# Sheet1.net
KiCad netlist of a schematic drawn in Altium Designer
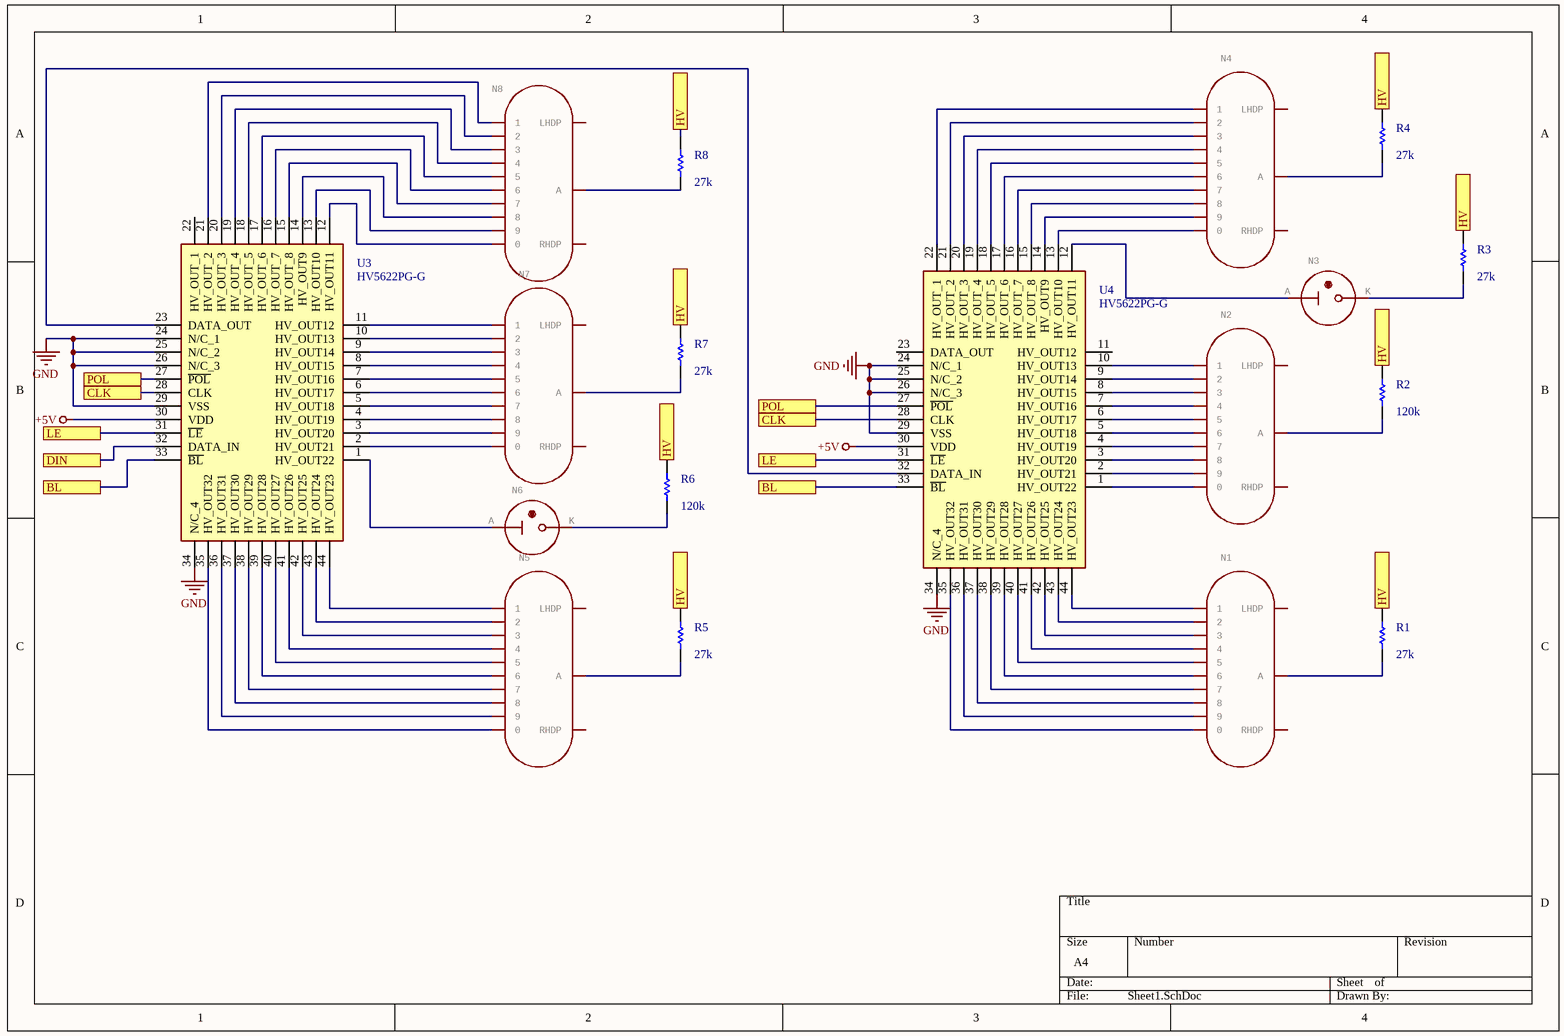
[diagram p0: Sheet1.SchDoc]

(export (version "E")
  (design (tool "Eeschema 10.0.6"))
  (components
    (comp (ref "N1")
      (value "IN-14: medium numeric frontview nixie tube")
      (footprint "IN-14")
      (fields (field (name "LIBRARYNAME") "nixies-us"))
      (libsource (lib "nixies-us.Library") (part "IN-14"))
    )
    (comp (ref "N2")
      (value "IN-14: medium numeric frontview nixie tube")
      (footprint "IN-14")
      (fields (field (name "LIBRARYNAME") "nixies-us"))
      (libsource (lib "nixies-us.Library") (part "IN-14"))
    )
    (comp (ref "N3")
      (value "IN-3: nixie bulb")
      (footprint "IN-3")
      (fields (field (name "LIBRARYNAME") "nixies-us"))
      (libsource (lib "nixies-us.Library") (part "IN-3"))
    )
    (comp (ref "N4")
      (value "IN-14: medium numeric frontview nixie tube")
      (footprint "IN-14")
      (fields (field (name "LIBRARYNAME") "nixies-us"))
      (libsource (lib "nixies-us.Library") (part "IN-14"))
    )
    (comp (ref "N5")
      (value "IN-14: medium numeric frontview nixie tube")
      (footprint "IN-14")
      (fields (field (name "LIBRARYNAME") "nixies-us"))
      (libsource (lib "nixies-us.Library") (part "IN-14"))
    )
    (comp (ref "N6")
      (value "IN-3: nixie bulb")
      (footprint "IN-3")
      (fields (field (name "LIBRARYNAME") "nixies-us"))
      (libsource (lib "nixies-us.Library") (part "IN-3"))
    )
    (comp (ref "N7")
      (value "IN-14: medium numeric frontview nixie tube")
      (footprint "IN-14")
      (fields (field (name "LIBRARYNAME") "nixies-us"))
      (libsource (lib "nixies-us.Library") (part "IN-14"))
    )
    (comp (ref "N8")
      (value "IN-14: medium numeric frontview nixie tube")
      (footprint "IN-14")
      (fields (field (name "LIBRARYNAME") "nixies-us"))
      (libsource (lib "nixies-us.Library") (part "IN-14"))
    )
    (comp (ref "R1")
      (value "27k")
      (footprint "AXIAL-0.3")
      (description "Resistor")
      (fields (field (name "PUBLISHER") "Altium Limited"))
      (libsource (lib "Miscellaneous Devices") (part "Res1"))
    )
    (comp (ref "R2")
      (value "120k")
      (footprint "AXIAL-0.3")
      (description "Resistor")
      (fields (field (name "PUBLISHER") "Altium Limited"))
      (libsource (lib "Miscellaneous Devices") (part "Res1"))
    )
    (comp (ref "R3")
      (value "27k")
      (footprint "AXIAL-0.3")
      (description "Resistor")
      (fields (field (name "PUBLISHER") "Altium Limited"))
      (libsource (lib "Miscellaneous Devices") (part "Res1"))
    )
    (comp (ref "R4")
      (value "27k")
      (footprint "AXIAL-0.3")
      (description "Resistor")
      (fields (field (name "PUBLISHER") "Altium Limited"))
      (libsource (lib "Miscellaneous Devices") (part "Res1"))
    )
    (comp (ref "R5")
      (value "27k")
      (footprint "AXIAL-0.3")
      (description "Resistor")
      (fields (field (name "PUBLISHER") "Altium Limited"))
      (libsource (lib "Miscellaneous Devices") (part "Res1"))
    )
    (comp (ref "R6")
      (value "120k")
      (footprint "AXIAL-0.3")
      (description "Resistor")
      (fields (field (name "PUBLISHER") "Altium Limited"))
      (libsource (lib "Miscellaneous Devices") (part "Res1"))
    )
    (comp (ref "R7")
      (value "27k")
      (footprint "AXIAL-0.3")
      (description "Resistor")
      (fields (field (name "PUBLISHER") "Altium Limited"))
      (libsource (lib "Miscellaneous Devices") (part "Res1"))
    )
    (comp (ref "R8")
      (value "27k")
      (footprint "AXIAL-0.3")
      (description "Resistor")
      (fields (field (name "PUBLISHER") "Altium Limited"))
      (libsource (lib "Miscellaneous Devices") (part "Res1"))
    )
    (comp (ref "U3")
      (value "HV5622PG-G")
      (footprint "SamacSys:QFP80P1390X1390X235-44N")
      (description "Integrated Circuit")
      (fields (field (name "MOUSER PART NUMBER") "689-HV5622PG-G"))
      (libsource (lib "*") (part "HV5622PG-G"))
    )
    (comp (ref "U4")
      (value "HV5622PG-G")
      (footprint "SamacSys:QFP80P1390X1390X235-44N")
      (description "Integrated Circuit")
      (fields (field (name "MOUSER PART NUMBER") "689-HV5622PG-G"))
      (libsource (lib "*") (part "HV5622PG-G"))
    )
  )
  (nets
    (net (code "1") (name "+5V") (class "Default")
      (node (ref "U3") (pin "30") (pinfunction "VDD_30") (pintype "passive"))
      (node (ref "U4") (pin "30") (pinfunction "VDD_30") (pintype "passive"))
    )
    (net (code "2") (name "/BL") (class "Default")
      (node (ref "U3") (pin "33") (pinfunction "~{BL}_33") (pintype "passive"))
      (node (ref "U4") (pin "33") (pinfunction "~{BL}_33") (pintype "passive"))
    )
    (net (code "3") (name "/CLK") (class "Default")
      (node (ref "U3") (pin "28") (pinfunction "CLK_28") (pintype "passive"))
      (node (ref "U4") (pin "28") (pinfunction "CLK_28") (pintype "passive"))
    )
    (net (code "4") (name "/DIN") (class "Default")
      (node (ref "U3") (pin "32") (pinfunction "DATA_IN_32") (pintype "passive"))
    )
    (net (code "5") (name "/HV") (class "Default")
      (node (ref "R1") (pin "1") (pinfunction "1_1") (pintype "passive"))
      (node (ref "R2") (pin "1") (pinfunction "1_1") (pintype "passive"))
      (node (ref "R3") (pin "1") (pinfunction "1_1") (pintype "passive"))
      (node (ref "R4") (pin "1") (pinfunction "1_1") (pintype "passive"))
      (node (ref "R5") (pin "1") (pinfunction "1_1") (pintype "passive"))
      (node (ref "R6") (pin "1") (pinfunction "1_1") (pintype "passive"))
      (node (ref "R7") (pin "1") (pinfunction "1_1") (pintype "passive"))
      (node (ref "R8") (pin "1") (pinfunction "1_1") (pintype "passive"))
    )
    (net (code "6") (name "/LE") (class "Default")
      (node (ref "U3") (pin "31") (pinfunction "~{LE}_31") (pintype "passive"))
      (node (ref "U4") (pin "31") (pinfunction "~{LE}_31") (pintype "passive"))
    )
    (net (code "7") (name "/POL") (class "Default")
      (node (ref "U3") (pin "27") (pinfunction "~{POL}_27") (pintype "passive"))
      (node (ref "U4") (pin "27") (pinfunction "~{POL}_27") (pintype "passive"))
    )
    (net (code "8") (name "GND") (class "Default")
      (node (ref "U3") (pin "24") (pinfunction "N/C_1_24") (pintype "passive"))
      (node (ref "U3") (pin "25") (pinfunction "N/C_2_25") (pintype "passive"))
      (node (ref "U3") (pin "26") (pinfunction "N/C_3_26") (pintype "passive"))
      (node (ref "U3") (pin "29") (pinfunction "VSS_29") (pintype "passive"))
      (node (ref "U3") (pin "34") (pinfunction "N/C_4_34") (pintype "passive"))
      (node (ref "U4") (pin "24") (pinfunction "N/C_1_24") (pintype "passive"))
      (node (ref "U4") (pin "25") (pinfunction "N/C_2_25") (pintype "passive"))
      (node (ref "U4") (pin "26") (pinfunction "N/C_3_26") (pintype "passive"))
      (node (ref "U4") (pin "29") (pinfunction "VSS_29") (pintype "passive"))
      (node (ref "U4") (pin "34") (pinfunction "N/C_4_34") (pintype "passive"))
    )
    (net (code "9") (name "Net-(N1-PadA)") (class "Default")
      (node (ref "N1") (pin "A") (pinfunction "A_A") (pintype "bidirectional"))
      (node (ref "R1") (pin "2") (pinfunction "2_2") (pintype "passive"))
    )
    (net (code "10") (name "Net-(N2-PadA)") (class "Default")
      (node (ref "N2") (pin "A") (pinfunction "A_A") (pintype "bidirectional"))
      (node (ref "R2") (pin "2") (pinfunction "2_2") (pintype "passive"))
    )
    (net (code "11") (name "Net-(N3-PadK)") (class "Default")
      (node (ref "N3") (pin "K") (pinfunction "K_K") (pintype "bidirectional"))
      (node (ref "R3") (pin "2") (pinfunction "2_2") (pintype "passive"))
    )
    (net (code "12") (name "Net-(N4-PadA)") (class "Default")
      (node (ref "N4") (pin "A") (pinfunction "A_A") (pintype "bidirectional"))
      (node (ref "R4") (pin "2") (pinfunction "2_2") (pintype "passive"))
    )
    (net (code "13") (name "Net-(N5-PadA)") (class "Default")
      (node (ref "N5") (pin "A") (pinfunction "A_A") (pintype "bidirectional"))
      (node (ref "R5") (pin "2") (pinfunction "2_2") (pintype "passive"))
    )
    (net (code "14") (name "Net-(N6-PadK)") (class "Default")
      (node (ref "N6") (pin "K") (pinfunction "K_K") (pintype "bidirectional"))
      (node (ref "R6") (pin "2") (pinfunction "2_2") (pintype "passive"))
    )
    (net (code "15") (name "Net-(N7-PadA)") (class "Default")
      (node (ref "N7") (pin "A") (pinfunction "A_A") (pintype "bidirectional"))
      (node (ref "R7") (pin "2") (pinfunction "2_2") (pintype "passive"))
    )
    (net (code "16") (name "Net-(N8-PadA)") (class "Default")
      (node (ref "N8") (pin "A") (pinfunction "A_A") (pintype "bidirectional"))
      (node (ref "R8") (pin "2") (pinfunction "2_2") (pintype "passive"))
    )
    (net (code "17") (name "Net-(U3-DATA_OUT)") (class "Default")
      (node (ref "U3") (pin "23") (pinfunction "DATA_OUT_23") (pintype "passive"))
      (node (ref "U4") (pin "32") (pinfunction "DATA_IN_32") (pintype "passive"))
    )
    (net (code "18") (name "Net-(U3-HV_OUT9)") (class "Default")
      (node (ref "N8") (pin "8") (pinfunction "8_8") (pintype "bidirectional"))
      (node (ref "U3") (pin "14") (pinfunction "HV_OUT9_14") (pintype "passive"))
    )
    (net (code "19") (name "Net-(U3-HV_OUT10)") (class "Default")
      (node (ref "N8") (pin "9") (pinfunction "9_9") (pintype "bidirectional"))
      (node (ref "U3") (pin "13") (pinfunction "HV_OUT10_13") (pintype "passive"))
    )
    (net (code "20") (name "Net-(U3-HV_OUT11)") (class "Default")
      (node (ref "N8") (pin "0") (pinfunction "0_0") (pintype "bidirectional"))
      (node (ref "U3") (pin "12") (pinfunction "HV_OUT11_12") (pintype "passive"))
    )
    (net (code "21") (name "Net-(U3-HV_OUT12)") (class "Default")
      (node (ref "N7") (pin "1") (pinfunction "1_1") (pintype "bidirectional"))
      (node (ref "U3") (pin "11") (pinfunction "HV_OUT12_11") (pintype "passive"))
    )
    (net (code "22") (name "Net-(U3-HV_OUT13)") (class "Default")
      (node (ref "N7") (pin "2") (pinfunction "2_2") (pintype "bidirectional"))
      (node (ref "U3") (pin "10") (pinfunction "HV_OUT13_10") (pintype "passive"))
    )
    (net (code "23") (name "Net-(U3-HV_OUT14)") (class "Default")
      (node (ref "N7") (pin "3") (pinfunction "3_3") (pintype "bidirectional"))
      (node (ref "U3") (pin "9") (pinfunction "HV_OUT14_9") (pintype "passive"))
    )
    (net (code "24") (name "Net-(U3-HV_OUT15)") (class "Default")
      (node (ref "N7") (pin "4") (pinfunction "4_4") (pintype "bidirectional"))
      (node (ref "U3") (pin "8") (pinfunction "HV_OUT15_8") (pintype "passive"))
    )
    (net (code "25") (name "Net-(U3-HV_OUT16)") (class "Default")
      (node (ref "N7") (pin "5") (pinfunction "5_5") (pintype "bidirectional"))
      (node (ref "U3") (pin "7") (pinfunction "HV_OUT16_7") (pintype "passive"))
    )
    (net (code "26") (name "Net-(U3-HV_OUT17)") (class "Default")
      (node (ref "N7") (pin "6") (pinfunction "6_6") (pintype "bidirectional"))
      (node (ref "U3") (pin "6") (pinfunction "HV_OUT17_6") (pintype "passive"))
    )
    (net (code "27") (name "Net-(U3-HV_OUT18)") (class "Default")
      (node (ref "N7") (pin "7") (pinfunction "7_7") (pintype "bidirectional"))
      (node (ref "U3") (pin "5") (pinfunction "HV_OUT18_5") (pintype "passive"))
    )
    (net (code "28") (name "Net-(U3-HV_OUT19)") (class "Default")
      (node (ref "N7") (pin "8") (pinfunction "8_8") (pintype "bidirectional"))
      (node (ref "U3") (pin "4") (pinfunction "HV_OUT19_4") (pintype "passive"))
    )
    (net (code "29") (name "Net-(U3-HV_OUT20)") (class "Default")
      (node (ref "N7") (pin "9") (pinfunction "9_9") (pintype "bidirectional"))
      (node (ref "U3") (pin "3") (pinfunction "HV_OUT20_3") (pintype "passive"))
    )
    (net (code "30") (name "Net-(U3-HV_OUT21)") (class "Default")
      (node (ref "N7") (pin "0") (pinfunction "0_0") (pintype "bidirectional"))
      (node (ref "U3") (pin "2") (pinfunction "HV_OUT21_2") (pintype "passive"))
    )
    (net (code "31") (name "Net-(U3-HV_OUT22)") (class "Default")
      (node (ref "N6") (pin "A") (pinfunction "A_A") (pintype "bidirectional"))
      (node (ref "U3") (pin "1") (pinfunction "HV_OUT22_1") (pintype "passive"))
    )
    (net (code "32") (name "Net-(U3-HV_OUT23)") (class "Default")
      (node (ref "N5") (pin "1") (pinfunction "1_1") (pintype "bidirectional"))
      (node (ref "U3") (pin "44") (pinfunction "HV_OUT23_44") (pintype "passive"))
    )
    (net (code "33") (name "Net-(U3-HV_OUT24)") (class "Default")
      (node (ref "N5") (pin "2") (pinfunction "2_2") (pintype "bidirectional"))
      (node (ref "U3") (pin "43") (pinfunction "HV_OUT24_43") (pintype "passive"))
    )
    (net (code "34") (name "Net-(U3-HV_OUT25)") (class "Default")
      (node (ref "N5") (pin "3") (pinfunction "3_3") (pintype "bidirectional"))
      (node (ref "U3") (pin "42") (pinfunction "HV_OUT25_42") (pintype "passive"))
    )
    (net (code "35") (name "Net-(U3-HV_OUT26)") (class "Default")
      (node (ref "N5") (pin "4") (pinfunction "4_4") (pintype "bidirectional"))
      (node (ref "U3") (pin "41") (pinfunction "HV_OUT26_41") (pintype "passive"))
    )
    (net (code "36") (name "Net-(U3-HV_OUT27)") (class "Default")
      (node (ref "N5") (pin "5") (pinfunction "5_5") (pintype "bidirectional"))
      (node (ref "U3") (pin "40") (pinfunction "HV_OUT27_40") (pintype "passive"))
    )
    (net (code "37") (name "Net-(U3-HV_OUT28)") (class "Default")
      (node (ref "N5") (pin "6") (pinfunction "6_6") (pintype "bidirectional"))
      (node (ref "U3") (pin "39") (pinfunction "HV_OUT28_39") (pintype "passive"))
    )
    (net (code "38") (name "Net-(U3-HV_OUT29)") (class "Default")
      (node (ref "N5") (pin "7") (pinfunction "7_7") (pintype "bidirectional"))
      (node (ref "U3") (pin "38") (pinfunction "HV_OUT29_38") (pintype "passive"))
    )
    (net (code "39") (name "Net-(U3-HV_OUT30)") (class "Default")
      (node (ref "N5") (pin "8") (pinfunction "8_8") (pintype "bidirectional"))
      (node (ref "U3") (pin "37") (pinfunction "HV_OUT30_37") (pintype "passive"))
    )
    (net (code "40") (name "Net-(U3-HV_OUT31)") (class "Default")
      (node (ref "N5") (pin "9") (pinfunction "9_9") (pintype "bidirectional"))
      (node (ref "U3") (pin "36") (pinfunction "HV_OUT31_36") (pintype "passive"))
    )
    (net (code "41") (name "Net-(U3-HV_OUT32)") (class "Default")
      (node (ref "N5") (pin "0") (pinfunction "0_0") (pintype "bidirectional"))
      (node (ref "U3") (pin "35") (pinfunction "HV_OUT32_35") (pintype "passive"))
    )
    (net (code "42") (name "Net-(U3-HV_OUT_2)") (class "Default")
      (node (ref "N8") (pin "1") (pinfunction "1_1") (pintype "bidirectional"))
      (node (ref "U3") (pin "21") (pinfunction "HV_OUT_2_21") (pintype "passive"))
    )
    (net (code "43") (name "Net-(U3-HV_OUT_3)") (class "Default")
      (node (ref "N8") (pin "2") (pinfunction "2_2") (pintype "bidirectional"))
      (node (ref "U3") (pin "20") (pinfunction "HV_OUT_3_20") (pintype "passive"))
    )
    (net (code "44") (name "Net-(U3-HV_OUT_4)") (class "Default")
      (node (ref "N8") (pin "3") (pinfunction "3_3") (pintype "bidirectional"))
      (node (ref "U3") (pin "19") (pinfunction "HV_OUT_4_19") (pintype "passive"))
    )
    (net (code "45") (name "Net-(U3-HV_OUT_5)") (class "Default")
      (node (ref "N8") (pin "4") (pinfunction "4_4") (pintype "bidirectional"))
      (node (ref "U3") (pin "18") (pinfunction "HV_OUT_5_18") (pintype "passive"))
    )
    (net (code "46") (name "Net-(U3-HV_OUT_6)") (class "Default")
      (node (ref "N8") (pin "5") (pinfunction "5_5") (pintype "bidirectional"))
      (node (ref "U3") (pin "17") (pinfunction "HV_OUT_6_17") (pintype "passive"))
    )
    (net (code "47") (name "Net-(U3-HV_OUT_7)") (class "Default")
      (node (ref "N8") (pin "6") (pinfunction "6_6") (pintype "bidirectional"))
      (node (ref "U3") (pin "16") (pinfunction "HV_OUT_7_16") (pintype "passive"))
    )
    (net (code "48") (name "Net-(U3-HV_OUT_8)") (class "Default")
      (node (ref "N8") (pin "7") (pinfunction "7_7") (pintype "bidirectional"))
      (node (ref "U3") (pin "15") (pinfunction "HV_OUT_8_15") (pintype "passive"))
    )
    (net (code "49") (name "Net-(U4-HV_OUT9)") (class "Default")
      (node (ref "N4") (pin "9") (pinfunction "9_9") (pintype "bidirectional"))
      (node (ref "U4") (pin "14") (pinfunction "HV_OUT9_14") (pintype "passive"))
    )
    (net (code "50") (name "Net-(U4-HV_OUT10)") (class "Default")
      (node (ref "N4") (pin "0") (pinfunction "0_0") (pintype "bidirectional"))
      (node (ref "U4") (pin "13") (pinfunction "HV_OUT10_13") (pintype "passive"))
    )
    (net (code "51") (name "Net-(U4-HV_OUT11)") (class "Default")
      (node (ref "N3") (pin "A") (pinfunction "A_A") (pintype "bidirectional"))
      (node (ref "U4") (pin "12") (pinfunction "HV_OUT11_12") (pintype "passive"))
    )
    (net (code "52") (name "Net-(U4-HV_OUT13)") (class "Default")
      (node (ref "N2") (pin "1") (pinfunction "1_1") (pintype "bidirectional"))
      (node (ref "U4") (pin "10") (pinfunction "HV_OUT13_10") (pintype "passive"))
    )
    (net (code "53") (name "Net-(U4-HV_OUT14)") (class "Default")
      (node (ref "N2") (pin "2") (pinfunction "2_2") (pintype "bidirectional"))
      (node (ref "U4") (pin "9") (pinfunction "HV_OUT14_9") (pintype "passive"))
    )
    (net (code "54") (name "Net-(U4-HV_OUT15)") (class "Default")
      (node (ref "N2") (pin "3") (pinfunction "3_3") (pintype "bidirectional"))
      (node (ref "U4") (pin "8") (pinfunction "HV_OUT15_8") (pintype "passive"))
    )
    (net (code "55") (name "Net-(U4-HV_OUT16)") (class "Default")
      (node (ref "N2") (pin "4") (pinfunction "4_4") (pintype "bidirectional"))
      (node (ref "U4") (pin "7") (pinfunction "HV_OUT16_7") (pintype "passive"))
    )
    (net (code "56") (name "Net-(U4-HV_OUT17)") (class "Default")
      (node (ref "N2") (pin "5") (pinfunction "5_5") (pintype "bidirectional"))
      (node (ref "U4") (pin "6") (pinfunction "HV_OUT17_6") (pintype "passive"))
    )
    (net (code "57") (name "Net-(U4-HV_OUT18)") (class "Default")
      (node (ref "N2") (pin "6") (pinfunction "6_6") (pintype "bidirectional"))
      (node (ref "U4") (pin "5") (pinfunction "HV_OUT18_5") (pintype "passive"))
    )
    (net (code "58") (name "Net-(U4-HV_OUT19)") (class "Default")
      (node (ref "N2") (pin "7") (pinfunction "7_7") (pintype "bidirectional"))
      (node (ref "U4") (pin "4") (pinfunction "HV_OUT19_4") (pintype "passive"))
    )
    (net (code "59") (name "Net-(U4-HV_OUT20)") (class "Default")
      (node (ref "N2") (pin "8") (pinfunction "8_8") (pintype "bidirectional"))
      (node (ref "U4") (pin "3") (pinfunction "HV_OUT20_3") (pintype "passive"))
    )
    (net (code "60") (name "Net-(U4-HV_OUT21)") (class "Default")
      (node (ref "N2") (pin "9") (pinfunction "9_9") (pintype "bidirectional"))
      (node (ref "U4") (pin "2") (pinfunction "HV_OUT21_2") (pintype "passive"))
    )
    (net (code "61") (name "Net-(U4-HV_OUT22)") (class "Default")
      (node (ref "N2") (pin "0") (pinfunction "0_0") (pintype "bidirectional"))
      (node (ref "U4") (pin "1") (pinfunction "HV_OUT22_1") (pintype "passive"))
    )
    (net (code "62") (name "Net-(U4-HV_OUT23)") (class "Default")
      (node (ref "N1") (pin "1") (pinfunction "1_1") (pintype "bidirectional"))
      (node (ref "U4") (pin "44") (pinfunction "HV_OUT23_44") (pintype "passive"))
    )
    (net (code "63") (name "Net-(U4-HV_OUT24)") (class "Default")
      (node (ref "N1") (pin "2") (pinfunction "2_2") (pintype "bidirectional"))
      (node (ref "U4") (pin "43") (pinfunction "HV_OUT24_43") (pintype "passive"))
    )
    (net (code "64") (name "Net-(U4-HV_OUT25)") (class "Default")
      (node (ref "N1") (pin "3") (pinfunction "3_3") (pintype "bidirectional"))
      (node (ref "U4") (pin "42") (pinfunction "HV_OUT25_42") (pintype "passive"))
    )
    (net (code "65") (name "Net-(U4-HV_OUT26)") (class "Default")
      (node (ref "N1") (pin "4") (pinfunction "4_4") (pintype "bidirectional"))
      (node (ref "U4") (pin "41") (pinfunction "HV_OUT26_41") (pintype "passive"))
    )
    (net (code "66") (name "Net-(U4-HV_OUT27)") (class "Default")
      (node (ref "N1") (pin "5") (pinfunction "5_5") (pintype "bidirectional"))
      (node (ref "U4") (pin "40") (pinfunction "HV_OUT27_40") (pintype "passive"))
    )
    (net (code "67") (name "Net-(U4-HV_OUT28)") (class "Default")
      (node (ref "N1") (pin "6") (pinfunction "6_6") (pintype "bidirectional"))
      (node (ref "U4") (pin "39") (pinfunction "HV_OUT28_39") (pintype "passive"))
    )
    (net (code "68") (name "Net-(U4-HV_OUT29)") (class "Default")
      (node (ref "N1") (pin "7") (pinfunction "7_7") (pintype "bidirectional"))
      (node (ref "U4") (pin "38") (pinfunction "HV_OUT29_38") (pintype "passive"))
    )
    (net (code "69") (name "Net-(U4-HV_OUT30)") (class "Default")
      (node (ref "N1") (pin "8") (pinfunction "8_8") (pintype "bidirectional"))
      (node (ref "U4") (pin "37") (pinfunction "HV_OUT30_37") (pintype "passive"))
    )
    (net (code "70") (name "Net-(U4-HV_OUT31)") (class "Default")
      (node (ref "N1") (pin "9") (pinfunction "9_9") (pintype "bidirectional"))
      (node (ref "U4") (pin "36") (pinfunction "HV_OUT31_36") (pintype "passive"))
    )
    (net (code "71") (name "Net-(U4-HV_OUT32)") (class "Default")
      (node (ref "N1") (pin "0") (pinfunction "0_0") (pintype "bidirectional"))
      (node (ref "U4") (pin "35") (pinfunction "HV_OUT32_35") (pintype "passive"))
    )
    (net (code "72") (name "Net-(U4-HV_OUT_1)") (class "Default")
      (node (ref "N4") (pin "1") (pinfunction "1_1") (pintype "bidirectional"))
      (node (ref "U4") (pin "22") (pinfunction "HV_OUT_1_22") (pintype "passive"))
    )
    (net (code "73") (name "Net-(U4-HV_OUT_2)") (class "Default")
      (node (ref "N4") (pin "2") (pinfunction "2_2") (pintype "bidirectional"))
      (node (ref "U4") (pin "21") (pinfunction "HV_OUT_2_21") (pintype "passive"))
    )
    (net (code "74") (name "Net-(U4-HV_OUT_3)") (class "Default")
      (node (ref "N4") (pin "3") (pinfunction "3_3") (pintype "bidirectional"))
      (node (ref "U4") (pin "20") (pinfunction "HV_OUT_3_20") (pintype "passive"))
    )
    (net (code "75") (name "Net-(U4-HV_OUT_4)") (class "Default")
      (node (ref "N4") (pin "4") (pinfunction "4_4") (pintype "bidirectional"))
      (node (ref "U4") (pin "19") (pinfunction "HV_OUT_4_19") (pintype "passive"))
    )
    (net (code "76") (name "Net-(U4-HV_OUT_5)") (class "Default")
      (node (ref "N4") (pin "5") (pinfunction "5_5") (pintype "bidirectional"))
      (node (ref "U4") (pin "18") (pinfunction "HV_OUT_5_18") (pintype "passive"))
    )
    (net (code "77") (name "Net-(U4-HV_OUT_6)") (class "Default")
      (node (ref "N4") (pin "6") (pinfunction "6_6") (pintype "bidirectional"))
      (node (ref "U4") (pin "17") (pinfunction "HV_OUT_6_17") (pintype "passive"))
    )
    (net (code "78") (name "Net-(U4-HV_OUT_7)") (class "Default")
      (node (ref "N4") (pin "7") (pinfunction "7_7") (pintype "bidirectional"))
      (node (ref "U4") (pin "16") (pinfunction "HV_OUT_7_16") (pintype "passive"))
    )
    (net (code "79") (name "Net-(U4-HV_OUT_8)") (class "Default")
      (node (ref "N4") (pin "8") (pinfunction "8_8") (pintype "bidirectional"))
      (node (ref "U4") (pin "15") (pinfunction "HV_OUT_8_15") (pintype "passive"))
    )
    (net (code "80") (name "unconnected-(N1-PadLHDP)") (class "Default")
      (node (ref "N1") (pin "LHDP") (pinfunction "LHDP_LHDP") (pintype "bidirectional"))
    )
    (net (code "81") (name "unconnected-(N1-PadRHDP)") (class "Default")
      (node (ref "N1") (pin "RHDP") (pinfunction "RHDP_RHDP") (pintype "bidirectional"))
    )
    (net (code "82") (name "unconnected-(N2-PadLHDP)") (class "Default")
      (node (ref "N2") (pin "LHDP") (pinfunction "LHDP_LHDP") (pintype "bidirectional"))
    )
    (net (code "83") (name "unconnected-(N2-PadRHDP)") (class "Default")
      (node (ref "N2") (pin "RHDP") (pinfunction "RHDP_RHDP") (pintype "bidirectional"))
    )
    (net (code "84") (name "unconnected-(N4-PadLHDP)") (class "Default")
      (node (ref "N4") (pin "LHDP") (pinfunction "LHDP_LHDP") (pintype "bidirectional"))
    )
    (net (code "85") (name "unconnected-(N4-PadRHDP)") (class "Default")
      (node (ref "N4") (pin "RHDP") (pinfunction "RHDP_RHDP") (pintype "bidirectional"))
    )
    (net (code "86") (name "unconnected-(N5-PadLHDP)") (class "Default")
      (node (ref "N5") (pin "LHDP") (pinfunction "LHDP_LHDP") (pintype "bidirectional"))
    )
    (net (code "87") (name "unconnected-(N5-PadRHDP)") (class "Default")
      (node (ref "N5") (pin "RHDP") (pinfunction "RHDP_RHDP") (pintype "bidirectional"))
    )
    (net (code "88") (name "unconnected-(N7-PadLHDP)") (class "Default")
      (node (ref "N7") (pin "LHDP") (pinfunction "LHDP_LHDP") (pintype "bidirectional"))
    )
    (net (code "89") (name "unconnected-(N7-PadRHDP)") (class "Default")
      (node (ref "N7") (pin "RHDP") (pinfunction "RHDP_RHDP") (pintype "bidirectional"))
    )
    (net (code "90") (name "unconnected-(N8-PadLHDP)") (class "Default")
      (node (ref "N8") (pin "LHDP") (pinfunction "LHDP_LHDP") (pintype "bidirectional"))
    )
    (net (code "91") (name "unconnected-(N8-PadRHDP)") (class "Default")
      (node (ref "N8") (pin "RHDP") (pinfunction "RHDP_RHDP") (pintype "bidirectional"))
    )
    (net (code "92") (name "unconnected-(U3-HV_OUT_1-Pad22)") (class "Default")
      (node (ref "U3") (pin "22") (pinfunction "HV_OUT_1_22") (pintype "passive"))
    )
    (net (code "93") (name "unconnected-(U4-DATA_OUT-Pad23)") (class "Default")
      (node (ref "U4") (pin "23") (pinfunction "DATA_OUT_23") (pintype "passive"))
    )
    (net (code "94") (name "unconnected-(U4-HV_OUT12-Pad11)") (class "Default")
      (node (ref "U4") (pin "11") (pinfunction "HV_OUT12_11") (pintype "passive"))
    )
  )
)
